# USB_To_Serial.net
KiCad netlist of a schematic drawn in Altium Designer
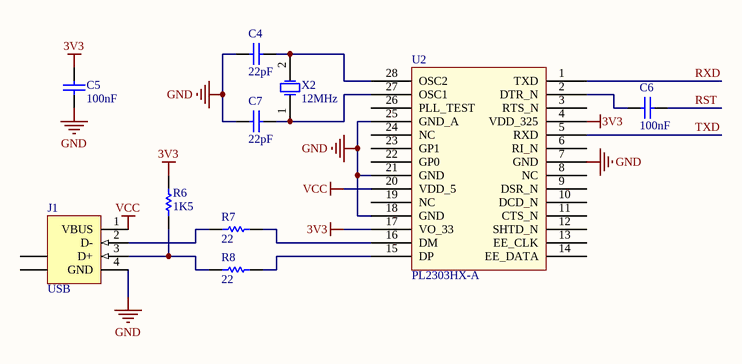
[diagram p0: USB To Serial.SchDoc]

(export (version "E")
  (design (tool "Eeschema 10.0.6"))
  (components
    (comp (ref "C4")
      (value "22pF")
      (footprint "toko-Embedded:C0805")
      (description "Capacitor")
      (fields (field (name "PUBLISHER") "Altium Limited"))
      (libsource (lib "Miscellaneous Devices") (part "Cap"))
    )
    (comp (ref "C5")
      (value "100nF")
      (footprint "toko-Embedded:C0805")
      (description "Capacitor")
      (fields (field (name "PUBLISHER") "Altium Limited"))
      (libsource (lib "Miscellaneous Devices") (part "Cap"))
    )
    (comp (ref "C6")
      (value "100nF")
      (footprint "toko-Embedded:C0805")
      (description "Capacitor")
      (fields (field (name "PUBLISHER") "Altium Limited"))
      (libsource (lib "Miscellaneous Devices") (part "Cap"))
    )
    (comp (ref "C7")
      (value "22pF")
      (footprint "toko-Embedded:C0805")
      (description "Capacitor")
      (fields (field (name "PUBLISHER") "Altium Limited"))
      (libsource (lib "Miscellaneous Devices") (part "Cap"))
    )
    (comp (ref "J1") (value "USB") (footprint "HDR1X4") (libsource (lib "Robotech") (part "USB")))
    (comp (ref "R6")
      (value "1K5")
      (footprint "toko-Embedded:R0805")
      (description "Resistor")
      (fields (field (name "PUBLISHER") "Altium Limited"))
      (libsource (lib "Miscellaneous Devices") (part "Res1"))
    )
    (comp (ref "R7")
      (value "22")
      (footprint "toko-Embedded:R0805")
      (description "Resistor")
      (fields (field (name "PUBLISHER") "Altium Limited"))
      (libsource (lib "Miscellaneous Devices") (part "Res1"))
    )
    (comp (ref "R8")
      (value "22")
      (footprint "toko-Embedded:R0805")
      (description "Resistor")
      (fields (field (name "PUBLISHER") "Altium Limited"))
      (libsource (lib "Miscellaneous Devices") (part "Res1"))
    )
    (comp (ref "U2")
      (value "PL2303HX-A")
      (footprint "toko-Embedded:SSOP-28")
      (libsource (lib "PL2303HX") (part "PL2303HX Rev. A"))
    )
    (comp (ref "X2")
      (value "12MHz")
      (footprint "toko-Embedded:HC49US")
      (description "Crystal Oscillator")
      (fields (field (name "PUBLISHER") "Altium Limited"))
      (libsource (lib "Miscellaneous Devices") (part "XTAL"))
    )
  )
  (nets
    (net (code "1") (name "/RST") (class "Default")
      (node (ref "C6") (pin "1") (pinfunction "1_1") (pintype "passive"))
    )
    (net (code "2") (name "/RXD") (class "Default")
      (node (ref "U2") (pin "1") (pinfunction "TXD_1") (pintype "passive"))
    )
    (net (code "3") (name "/TXD") (class "Default")
      (node (ref "U2") (pin "5") (pinfunction "RXD_5") (pintype "passive"))
    )
    (net (code "4") (name "3V3") (class "Default")
      (node (ref "C5") (pin "2") (pinfunction "2_2") (pintype "passive"))
      (node (ref "R6") (pin "2") (pinfunction "2_2") (pintype "passive"))
      (node (ref "U2") (pin "17") (pinfunction "VO_33_17") (pintype "passive"))
      (node (ref "U2") (pin "4") (pinfunction "VDD_325_4") (pintype "passive"))
    )
    (net (code "5") (name "GND") (class "Default")
      (node (ref "C4") (pin "1") (pinfunction "1_1") (pintype "passive"))
      (node (ref "C5") (pin "1") (pinfunction "1_1") (pintype "passive"))
      (node (ref "C7") (pin "1") (pinfunction "1_1") (pintype "passive"))
      (node (ref "J1") (pin "4") (pinfunction "GND_4") (pintype "power_in"))
      (node (ref "U2") (pin "18") (pinfunction "GND_18") (pintype "passive"))
      (node (ref "U2") (pin "21") (pinfunction "GND_21") (pintype "passive"))
      (node (ref "U2") (pin "25") (pinfunction "GND_A_25") (pintype "passive"))
      (node (ref "U2") (pin "7") (pinfunction "GND_7") (pintype "passive"))
    )
    (net (code "6") (name "Net-(J1-D+)") (class "Default")
      (node (ref "J1") (pin "3") (pinfunction "D+_3") (pintype "input"))
      (node (ref "R6") (pin "1") (pinfunction "1_1") (pintype "passive"))
      (node (ref "R8") (pin "1") (pinfunction "1_1") (pintype "passive"))
    )
    (net (code "7") (name "Net-(J1-D-)") (class "Default")
      (node (ref "J1") (pin "2") (pinfunction "D-_2") (pintype "input"))
      (node (ref "R7") (pin "1") (pinfunction "1_1") (pintype "passive"))
    )
    (net (code "8") (name "Net-(U2-DM)") (class "Default")
      (node (ref "R7") (pin "2") (pinfunction "2_2") (pintype "passive"))
      (node (ref "U2") (pin "16") (pinfunction "DM_16") (pintype "passive"))
    )
    (net (code "9") (name "Net-(U2-DP)") (class "Default")
      (node (ref "R8") (pin "2") (pinfunction "2_2") (pintype "passive"))
      (node (ref "U2") (pin "15") (pinfunction "DP_15") (pintype "passive"))
    )
    (net (code "10") (name "Net-(U2-DTR_N)") (class "Default")
      (node (ref "C6") (pin "2") (pinfunction "2_2") (pintype "passive"))
      (node (ref "U2") (pin "2") (pinfunction "DTR_N_2") (pintype "passive"))
    )
    (net (code "11") (name "Net-(U2-OSC1)") (class "Default")
      (node (ref "C7") (pin "2") (pinfunction "2_2") (pintype "passive"))
      (node (ref "U2") (pin "27") (pinfunction "OSC1_27") (pintype "passive"))
      (node (ref "X2") (pin "1") (pinfunction "OSC1_1") (pintype "passive"))
    )
    (net (code "12") (name "Net-(U2-OSC2)") (class "Default")
      (node (ref "C4") (pin "2") (pinfunction "2_2") (pintype "passive"))
      (node (ref "U2") (pin "28") (pinfunction "OSC2_28") (pintype "passive"))
      (node (ref "X2") (pin "2") (pinfunction "OSC2_2") (pintype "passive"))
    )
    (net (code "13") (name "VCC") (class "Default")
      (node (ref "J1") (pin "1") (pinfunction "VBUS_1") (pintype "power_in"))
      (node (ref "U2") (pin "20") (pinfunction "VDD_5_20") (pintype "passive"))
    )
    (net (code "14") (name "unconnected-(J1-SHLD-Pad5)") (class "Default")
      (node (ref "J1") (pin "5") (pinfunction "SHLD_5") (pintype "passive"))
    )
    (net (code "15") (name "unconnected-(J1-SHLD-Pad6)") (class "Default")
      (node (ref "J1") (pin "6") (pinfunction "SHLD_6") (pintype "passive"))
    )
    (net (code "16") (name "unconnected-(U2-CTS_N-Pad11)") (class "Default")
      (node (ref "U2") (pin "11") (pinfunction "CTS_N_11") (pintype "passive"))
    )
    (net (code "17") (name "unconnected-(U2-DCD_N-Pad10)") (class "Default")
      (node (ref "U2") (pin "10") (pinfunction "DCD_N_10") (pintype "passive"))
    )
    (net (code "18") (name "unconnected-(U2-DSR_N-Pad9)") (class "Default")
      (node (ref "U2") (pin "9") (pinfunction "DSR_N_9") (pintype "passive"))
    )
    (net (code "19") (name "unconnected-(U2-EE_CLK-Pad13)") (class "Default")
      (node (ref "U2") (pin "13") (pinfunction "EE_CLK_13") (pintype "passive"))
    )
    (net (code "20") (name "unconnected-(U2-EE_DATA-Pad14)") (class "Default")
      (node (ref "U2") (pin "14") (pinfunction "EE_DATA_14") (pintype "passive"))
    )
    (net (code "21") (name "unconnected-(U2-GP0-Pad22)") (class "Default")
      (node (ref "U2") (pin "22") (pinfunction "GP0_22") (pintype "passive"))
    )
    (net (code "22") (name "unconnected-(U2-GP1-Pad23)") (class "Default")
      (node (ref "U2") (pin "23") (pinfunction "GP1_23") (pintype "passive"))
    )
    (net (code "23") (name "unconnected-(U2-NC-Pad8)") (class "Default")
      (node (ref "U2") (pin "8") (pinfunction "NC_8") (pintype "passive"))
    )
    (net (code "24") (name "unconnected-(U2-NC-Pad19)") (class "Default")
      (node (ref "U2") (pin "19") (pinfunction "NC_19") (pintype "passive"))
    )
    (net (code "25") (name "unconnected-(U2-NC-Pad24)") (class "Default")
      (node (ref "U2") (pin "24") (pinfunction "NC_24") (pintype "passive"))
    )
    (net (code "26") (name "unconnected-(U2-PLL_TEST-Pad26)") (class "Default")
      (node (ref "U2") (pin "26") (pinfunction "PLL_TEST_26") (pintype "passive"))
    )
    (net (code "27") (name "unconnected-(U2-RI_N-Pad6)") (class "Default")
      (node (ref "U2") (pin "6") (pinfunction "RI_N_6") (pintype "passive"))
    )
    (net (code "28") (name "unconnected-(U2-RTS_N-Pad3)") (class "Default")
      (node (ref "U2") (pin "3") (pinfunction "RTS_N_3") (pintype "passive"))
    )
    (net (code "29") (name "unconnected-(U2-SHTD_N-Pad12)") (class "Default")
      (node (ref "U2") (pin "12") (pinfunction "SHTD_N_12") (pintype "passive"))
    )
  )
)
